# triode_control_board.net
KiCad netlist of a schematic drawn in EAGLE
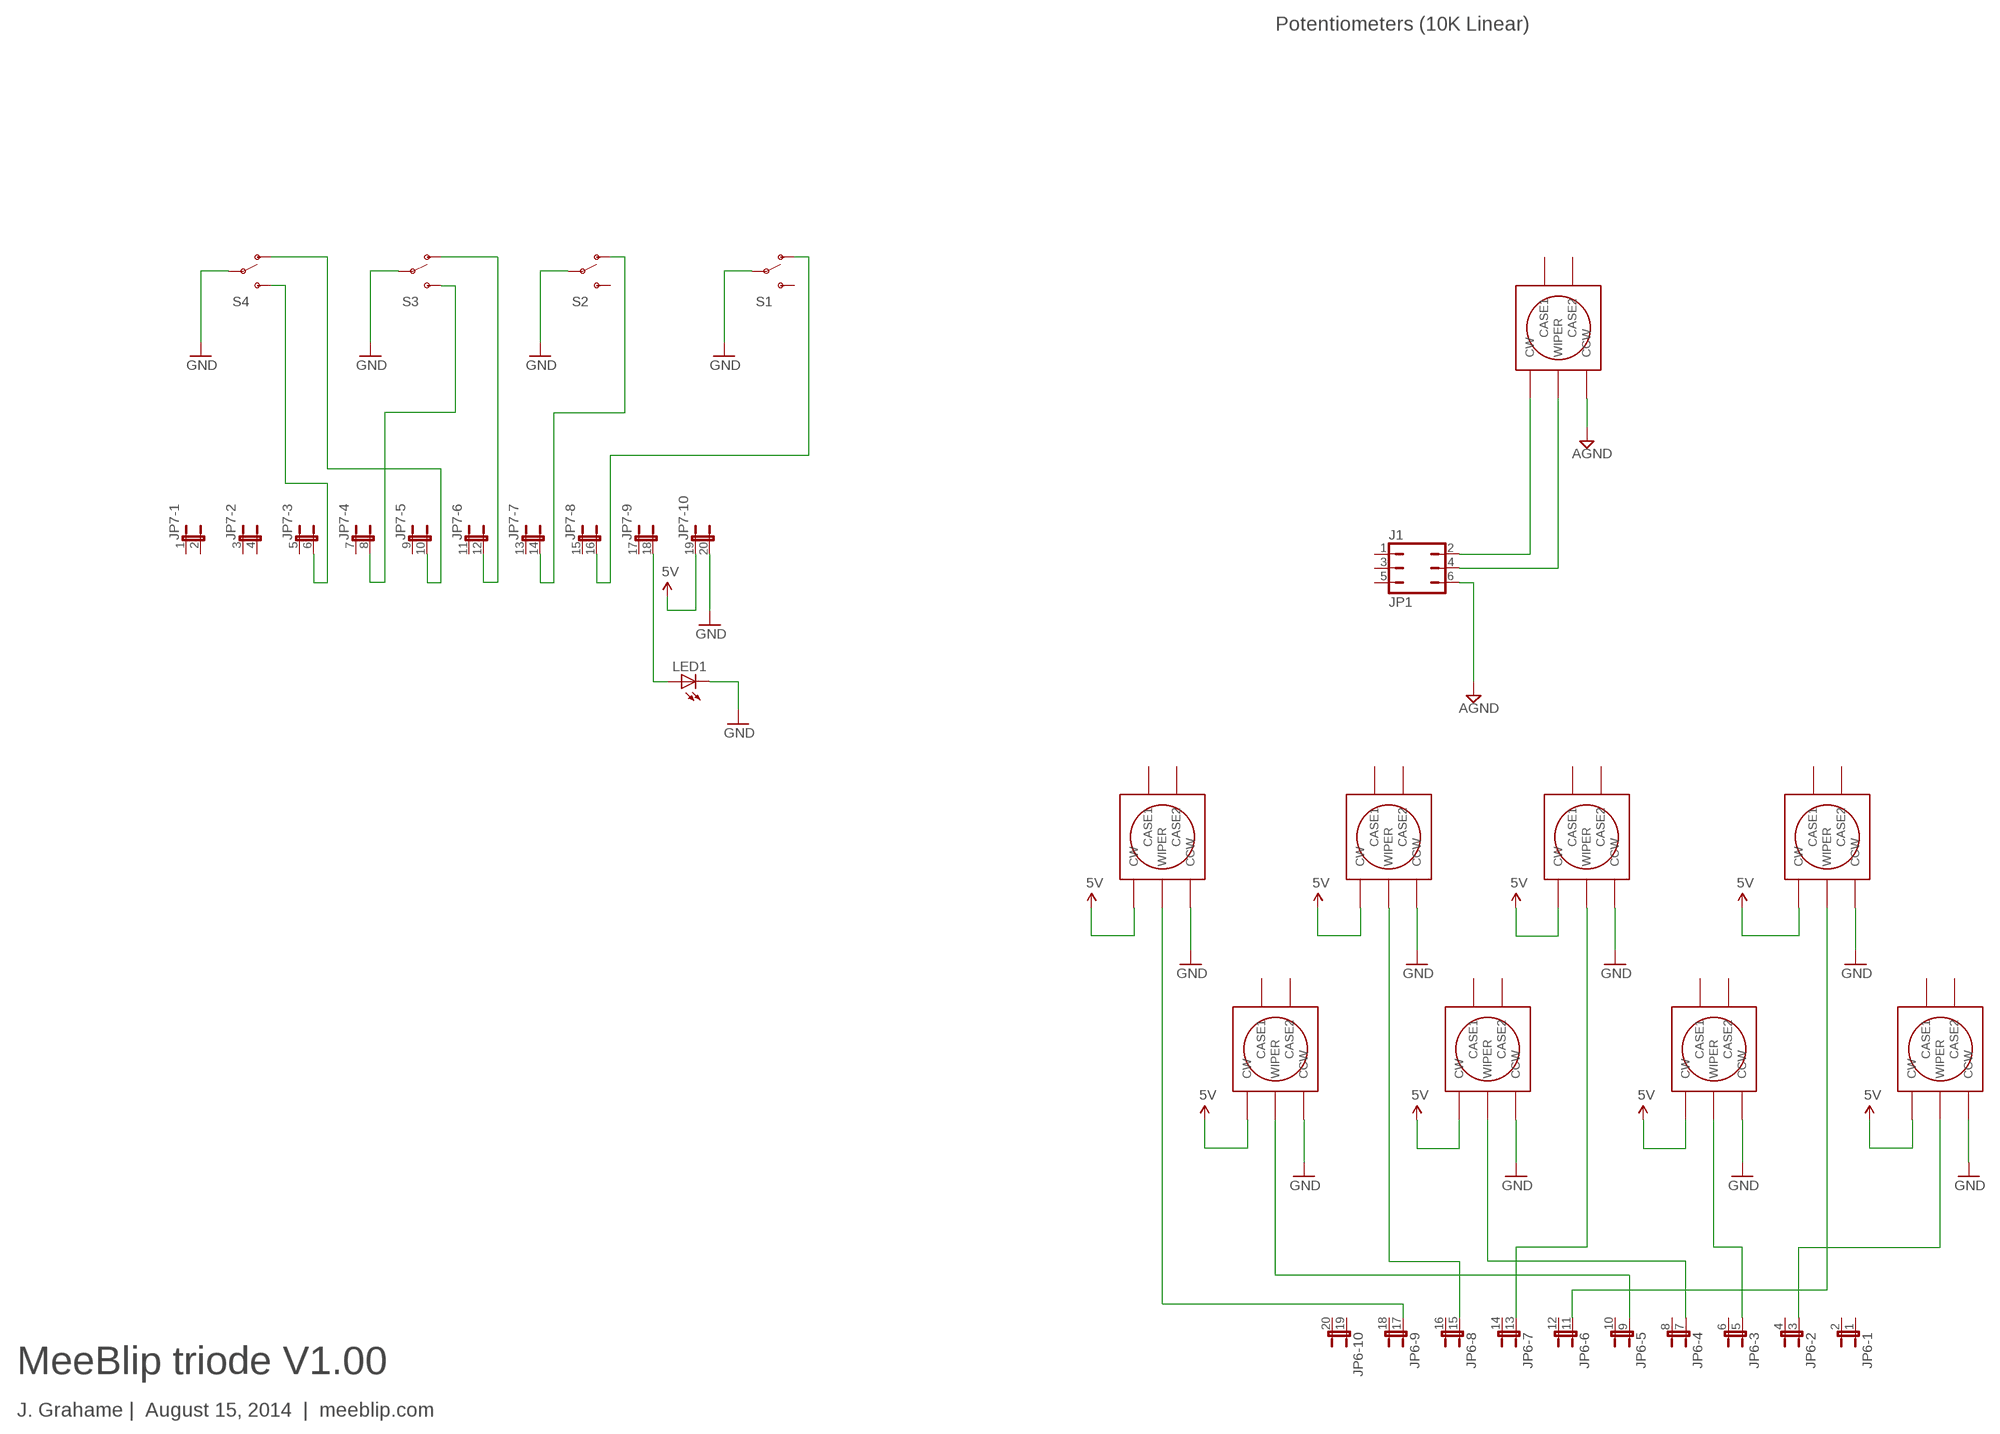
[diagram p0: schematic, sheet 1]

(export (version "E")
  (design (tool "Eeschema 10.0.6"))
  (components
    (comp (ref "J1")
      (value "JP1")
      (footprint "eagle-import:JP3Q")
      (libsource (lib "eagle-import") (part "JP3Q"))
    )
    (comp (ref "JP6")
      (value "JP10QE")
      (footprint "eagle-import:JP10Q")
      (libsource (lib "eagle-import") (part "JP10QE"))
    )
    (comp (ref "JP7")
      (value "JP10QE")
      (footprint "eagle-import:JP10Q")
      (libsource (lib "eagle-import") (part "JP10QE"))
    )
    (comp (ref "LED1")
      (value "LED3MM")
      (footprint "eagle-import:LED3MM")
      (libsource (lib "eagle-import") (part "LED3MM"))
    )
    (comp (ref "POT1")
      (value "VACOLOCO_EVUFRK09_POT")
      (footprint "eagle-import:VACOLOCO_EVUF")
      (libsource (lib "eagle-import") (part "VACOLOCO_EVUFRK09_POT"))
    )
    (comp (ref "POT2")
      (value "VACOLOCO_EVUFRK09_POT")
      (footprint "eagle-import:VACOLOCO_EVUF")
      (libsource (lib "eagle-import") (part "VACOLOCO_EVUFRK09_POT"))
    )
    (comp (ref "POT3")
      (value "VACOLOCO_EVUFRK09_POT")
      (footprint "eagle-import:VACOLOCO_EVUF")
      (libsource (lib "eagle-import") (part "VACOLOCO_EVUFRK09_POT"))
    )
    (comp (ref "POT4")
      (value "VACOLOCO_EVUFRK09_POT")
      (footprint "eagle-import:VACOLOCO_EVUF")
      (libsource (lib "eagle-import") (part "VACOLOCO_EVUFRK09_POT"))
    )
    (comp (ref "POT5")
      (value "VACOLOCO_EVUFRK09_POT")
      (footprint "eagle-import:VACOLOCO_EVUF")
      (libsource (lib "eagle-import") (part "VACOLOCO_EVUFRK09_POT"))
    )
    (comp (ref "POT6")
      (value "VACOLOCO_EVUFRK09_POT")
      (footprint "eagle-import:VACOLOCO_EVUF")
      (libsource (lib "eagle-import") (part "VACOLOCO_EVUFRK09_POT"))
    )
    (comp (ref "POT7")
      (value "VACOLOCO_EVUFRK09_POT")
      (footprint "eagle-import:VACOLOCO_EVUF")
      (libsource (lib "eagle-import") (part "VACOLOCO_EVUFRK09_POT"))
    )
    (comp (ref "POT8")
      (value "VACOLOCO_EVUFRK09_POT")
      (footprint "eagle-import:VACOLOCO_EVUF")
      (libsource (lib "eagle-import") (part "VACOLOCO_EVUFRK09_POT"))
    )
    (comp (ref "POT9")
      (value "VACOLOCO_EVUFRK09_POT")
      (footprint "eagle-import:VACOLOCO_EVUF")
      (libsource (lib "eagle-import") (part "VACOLOCO_EVUFRK09_POT"))
    )
    (comp (ref "S1")
      (value "SWITCH-SPDT")
      (footprint "eagle-import:MTS-102-A2")
      (libsource (lib "eagle-import") (part "SWITCH-SPDT"))
    )
    (comp (ref "S2")
      (value "SWITCH-SPDT")
      (footprint "eagle-import:MTS-102-A2")
      (libsource (lib "eagle-import") (part "SWITCH-SPDT"))
    )
    (comp (ref "S3")
      (value "SWITCH-SPDT")
      (footprint "eagle-import:MTS-102-A2")
      (libsource (lib "eagle-import") (part "SWITCH-SPDT"))
    )
    (comp (ref "S4")
      (value "SWITCH-SPDT")
      (footprint "eagle-import:MTS-102-A2")
      (libsource (lib "eagle-import") (part "SWITCH-SPDT"))
    )
  )
  (nets
    (net (code "1") (name "5V") (class "Default")
      (node (ref "JP7") (pin "19") (pinfunction "1_19") (pintype "passive"))
      (node (ref "POT2") (pin "CW") (pinfunction "CW_CW") (pintype "bidirectional"))
      (node (ref "POT3") (pin "CW") (pinfunction "CW_CW") (pintype "bidirectional"))
      (node (ref "POT4") (pin "CW") (pinfunction "CW_CW") (pintype "bidirectional"))
      (node (ref "POT5") (pin "CW") (pinfunction "CW_CW") (pintype "bidirectional"))
      (node (ref "POT6") (pin "CW") (pinfunction "CW_CW") (pintype "bidirectional"))
      (node (ref "POT7") (pin "CW") (pinfunction "CW_CW") (pintype "bidirectional"))
      (node (ref "POT8") (pin "CW") (pinfunction "CW_CW") (pintype "bidirectional"))
      (node (ref "POT9") (pin "CW") (pinfunction "CW_CW") (pintype "bidirectional"))
    )
    (net (code "2") (name "AGND") (class "Default")
      (node (ref "J1") (pin "6") (pinfunction "6_6") (pintype "passive"))
      (node (ref "POT1") (pin "CCW") (pinfunction "CCW_CCW") (pintype "bidirectional"))
    )
    (net (code "3") (name "GND") (class "Default")
      (node (ref "JP7") (pin "20") (pinfunction "2_20") (pintype "passive"))
      (node (ref "LED1") (pin "K") (pinfunction "C_K") (pintype "passive"))
      (node (ref "POT2") (pin "CCW") (pinfunction "CCW_CCW") (pintype "bidirectional"))
      (node (ref "POT3") (pin "CCW") (pinfunction "CCW_CCW") (pintype "bidirectional"))
      (node (ref "POT4") (pin "CCW") (pinfunction "CCW_CCW") (pintype "bidirectional"))
      (node (ref "POT5") (pin "CCW") (pinfunction "CCW_CCW") (pintype "bidirectional"))
      (node (ref "POT6") (pin "CCW") (pinfunction "CCW_CCW") (pintype "bidirectional"))
      (node (ref "POT7") (pin "CCW") (pinfunction "CCW_CCW") (pintype "bidirectional"))
      (node (ref "POT8") (pin "CCW") (pinfunction "CCW_CCW") (pintype "bidirectional"))
      (node (ref "POT9") (pin "CCW") (pinfunction "CCW_CCW") (pintype "bidirectional"))
      (node (ref "S1") (pin "2") (pinfunction "P_2") (pintype "passive"))
      (node (ref "S2") (pin "2") (pinfunction "P_2") (pintype "passive"))
      (node (ref "S3") (pin "2") (pinfunction "P_2") (pintype "passive"))
      (node (ref "S4") (pin "2") (pinfunction "P_2") (pintype "passive"))
    )
    (net (code "4") (name "Net-(J1-Pad2)") (class "Default")
      (node (ref "J1") (pin "2") (pinfunction "2_2") (pintype "passive"))
      (node (ref "POT1") (pin "CW") (pinfunction "CW_CW") (pintype "bidirectional"))
    )
    (net (code "5") (name "Net-(J1-Pad4)") (class "Default")
      (node (ref "J1") (pin "4") (pinfunction "4_4") (pintype "passive"))
      (node (ref "POT1") (pin "WIPER") (pinfunction "WIPER_WIPER") (pintype "bidirectional"))
    )
    (net (code "6") (name "Net-(JP6C-1)") (class "Default")
      (node (ref "JP6") (pin "3") (pinfunction "1_3") (pintype "passive"))
      (node (ref "POT9") (pin "WIPER") (pinfunction "WIPER_WIPER") (pintype "bidirectional"))
    )
    (net (code "7") (name "Net-(JP6D-1)") (class "Default")
      (node (ref "JP6") (pin "5") (pinfunction "1_5") (pintype "passive"))
      (node (ref "POT8") (pin "WIPER") (pinfunction "WIPER_WIPER") (pintype "bidirectional"))
    )
    (net (code "8") (name "Net-(JP6E-1)") (class "Default")
      (node (ref "JP6") (pin "7") (pinfunction "1_7") (pintype "passive"))
      (node (ref "POT7") (pin "WIPER") (pinfunction "WIPER_WIPER") (pintype "bidirectional"))
    )
    (net (code "9") (name "Net-(JP6F-1)") (class "Default")
      (node (ref "JP6") (pin "9") (pinfunction "1_9") (pintype "passive"))
      (node (ref "POT6") (pin "WIPER") (pinfunction "WIPER_WIPER") (pintype "bidirectional"))
    )
    (net (code "10") (name "Net-(JP6G-1)") (class "Default")
      (node (ref "JP6") (pin "11") (pinfunction "1_11") (pintype "passive"))
      (node (ref "POT5") (pin "WIPER") (pinfunction "WIPER_WIPER") (pintype "bidirectional"))
    )
    (net (code "11") (name "Net-(JP6H-1)") (class "Default")
      (node (ref "JP6") (pin "13") (pinfunction "1_13") (pintype "passive"))
      (node (ref "POT4") (pin "WIPER") (pinfunction "WIPER_WIPER") (pintype "bidirectional"))
    )
    (net (code "12") (name "Net-(JP6I-1)") (class "Default")
      (node (ref "JP6") (pin "15") (pinfunction "1_15") (pintype "passive"))
      (node (ref "POT3") (pin "WIPER") (pinfunction "WIPER_WIPER") (pintype "bidirectional"))
    )
    (net (code "13") (name "Net-(JP6J-1)") (class "Default")
      (node (ref "JP6") (pin "17") (pinfunction "1_17") (pintype "passive"))
      (node (ref "POT2") (pin "WIPER") (pinfunction "WIPER_WIPER") (pintype "bidirectional"))
    )
    (net (code "14") (name "Net-(JP7D-2)") (class "Default")
      (node (ref "JP7") (pin "6") (pinfunction "2_6") (pintype "passive"))
      (node (ref "S4") (pin "3") (pinfunction "S_3") (pintype "passive"))
    )
    (net (code "15") (name "Net-(JP7E-2)") (class "Default")
      (node (ref "JP7") (pin "8") (pinfunction "2_8") (pintype "passive"))
      (node (ref "S3") (pin "3") (pinfunction "S_3") (pintype "passive"))
    )
    (net (code "16") (name "Net-(JP7F-2)") (class "Default")
      (node (ref "JP7") (pin "10") (pinfunction "2_10") (pintype "passive"))
      (node (ref "S4") (pin "1") (pinfunction "O_1") (pintype "passive"))
    )
    (net (code "17") (name "Net-(JP7G-2)") (class "Default")
      (node (ref "JP7") (pin "12") (pinfunction "2_12") (pintype "passive"))
      (node (ref "S3") (pin "1") (pinfunction "O_1") (pintype "passive"))
    )
    (net (code "18") (name "Net-(JP7H-2)") (class "Default")
      (node (ref "JP7") (pin "14") (pinfunction "2_14") (pintype "passive"))
      (node (ref "S2") (pin "1") (pinfunction "O_1") (pintype "passive"))
    )
    (net (code "19") (name "Net-(JP7I-2)") (class "Default")
      (node (ref "JP7") (pin "16") (pinfunction "2_16") (pintype "passive"))
      (node (ref "S1") (pin "1") (pinfunction "O_1") (pintype "passive"))
    )
    (net (code "20") (name "Net-(JP7J-2)") (class "Default")
      (node (ref "JP7") (pin "18") (pinfunction "2_18") (pintype "passive"))
      (node (ref "LED1") (pin "A") (pinfunction "A_A") (pintype "passive"))
    )
    (net (code "21") (name "unconnected-(J1-Pad1)") (class "Default")
      (node (ref "J1") (pin "1") (pinfunction "1_1") (pintype "passive"))
    )
    (net (code "22") (name "unconnected-(J1-Pad3)") (class "Default")
      (node (ref "J1") (pin "3") (pinfunction "3_3") (pintype "passive"))
    )
    (net (code "23") (name "unconnected-(J1-Pad5)") (class "Default")
      (node (ref "J1") (pin "5") (pinfunction "5_5") (pintype "passive"))
    )
    (net (code "24") (name "unconnected-(JP6-Pad1)") (class "Default")
      (node (ref "JP6") (pin "1") (pinfunction "1_1") (pintype "passive"))
    )
    (net (code "25") (name "unconnected-(JP6-Pad2)") (class "Default")
      (node (ref "JP6") (pin "2") (pinfunction "2_2") (pintype "passive"))
    )
    (net (code "26") (name "unconnected-(JP6B-1-Pad19)") (class "Default")
      (node (ref "JP6") (pin "19") (pinfunction "1_19") (pintype "passive"))
    )
    (net (code "27") (name "unconnected-(JP6B-2-Pad20)") (class "Default")
      (node (ref "JP6") (pin "20") (pinfunction "2_20") (pintype "passive"))
    )
    (net (code "28") (name "unconnected-(JP6C-2-Pad4)") (class "Default")
      (node (ref "JP6") (pin "4") (pinfunction "2_4") (pintype "passive"))
    )
    (net (code "29") (name "unconnected-(JP6D-2-Pad6)") (class "Default")
      (node (ref "JP6") (pin "6") (pinfunction "2_6") (pintype "passive"))
    )
    (net (code "30") (name "unconnected-(JP6E-2-Pad8)") (class "Default")
      (node (ref "JP6") (pin "8") (pinfunction "2_8") (pintype "passive"))
    )
    (net (code "31") (name "unconnected-(JP6F-2-Pad10)") (class "Default")
      (node (ref "JP6") (pin "10") (pinfunction "2_10") (pintype "passive"))
    )
    (net (code "32") (name "unconnected-(JP6G-2-Pad12)") (class "Default")
      (node (ref "JP6") (pin "12") (pinfunction "2_12") (pintype "passive"))
    )
    (net (code "33") (name "unconnected-(JP6H-2-Pad14)") (class "Default")
      (node (ref "JP6") (pin "14") (pinfunction "2_14") (pintype "passive"))
    )
    (net (code "34") (name "unconnected-(JP6I-2-Pad16)") (class "Default")
      (node (ref "JP6") (pin "16") (pinfunction "2_16") (pintype "passive"))
    )
    (net (code "35") (name "unconnected-(JP6J-2-Pad18)") (class "Default")
      (node (ref "JP6") (pin "18") (pinfunction "2_18") (pintype "passive"))
    )
    (net (code "36") (name "unconnected-(JP7-Pad1)") (class "Default")
      (node (ref "JP7") (pin "1") (pinfunction "1_1") (pintype "passive"))
    )
    (net (code "37") (name "unconnected-(JP7-Pad2)") (class "Default")
      (node (ref "JP7") (pin "2") (pinfunction "2_2") (pintype "passive"))
    )
    (net (code "38") (name "unconnected-(JP7C-1-Pad3)") (class "Default")
      (node (ref "JP7") (pin "3") (pinfunction "1_3") (pintype "passive"))
    )
    (net (code "39") (name "unconnected-(JP7C-2-Pad4)") (class "Default")
      (node (ref "JP7") (pin "4") (pinfunction "2_4") (pintype "passive"))
    )
    (net (code "40") (name "unconnected-(JP7D-1-Pad5)") (class "Default")
      (node (ref "JP7") (pin "5") (pinfunction "1_5") (pintype "passive"))
    )
    (net (code "41") (name "unconnected-(JP7E-1-Pad7)") (class "Default")
      (node (ref "JP7") (pin "7") (pinfunction "1_7") (pintype "passive"))
    )
    (net (code "42") (name "unconnected-(JP7F-1-Pad9)") (class "Default")
      (node (ref "JP7") (pin "9") (pinfunction "1_9") (pintype "passive"))
    )
    (net (code "43") (name "unconnected-(JP7G-1-Pad11)") (class "Default")
      (node (ref "JP7") (pin "11") (pinfunction "1_11") (pintype "passive"))
    )
    (net (code "44") (name "unconnected-(JP7H-1-Pad13)") (class "Default")
      (node (ref "JP7") (pin "13") (pinfunction "1_13") (pintype "passive"))
    )
    (net (code "45") (name "unconnected-(JP7I-1-Pad15)") (class "Default")
      (node (ref "JP7") (pin "15") (pinfunction "1_15") (pintype "passive"))
    )
    (net (code "46") (name "unconnected-(JP7J-1-Pad17)") (class "Default")
      (node (ref "JP7") (pin "17") (pinfunction "1_17") (pintype "passive"))
    )
    (net (code "47") (name "unconnected-(POT1-PadCASE1)") (class "Default")
      (node (ref "POT1") (pin "CASE1") (pinfunction "CASE1_CASE1") (pintype "bidirectional"))
    )
    (net (code "48") (name "unconnected-(POT1-PadCASE2)") (class "Default")
      (node (ref "POT1") (pin "CASE2") (pinfunction "CASE2_CASE2") (pintype "bidirectional"))
    )
    (net (code "49") (name "unconnected-(POT2-PadCASE1)") (class "Default")
      (node (ref "POT2") (pin "CASE1") (pinfunction "CASE1_CASE1") (pintype "bidirectional"))
    )
    (net (code "50") (name "unconnected-(POT2-PadCASE2)") (class "Default")
      (node (ref "POT2") (pin "CASE2") (pinfunction "CASE2_CASE2") (pintype "bidirectional"))
    )
    (net (code "51") (name "unconnected-(POT3-PadCASE1)") (class "Default")
      (node (ref "POT3") (pin "CASE1") (pinfunction "CASE1_CASE1") (pintype "bidirectional"))
    )
    (net (code "52") (name "unconnected-(POT3-PadCASE2)") (class "Default")
      (node (ref "POT3") (pin "CASE2") (pinfunction "CASE2_CASE2") (pintype "bidirectional"))
    )
    (net (code "53") (name "unconnected-(POT4-PadCASE1)") (class "Default")
      (node (ref "POT4") (pin "CASE1") (pinfunction "CASE1_CASE1") (pintype "bidirectional"))
    )
    (net (code "54") (name "unconnected-(POT4-PadCASE2)") (class "Default")
      (node (ref "POT4") (pin "CASE2") (pinfunction "CASE2_CASE2") (pintype "bidirectional"))
    )
    (net (code "55") (name "unconnected-(POT5-PadCASE1)") (class "Default")
      (node (ref "POT5") (pin "CASE1") (pinfunction "CASE1_CASE1") (pintype "bidirectional"))
    )
    (net (code "56") (name "unconnected-(POT5-PadCASE2)") (class "Default")
      (node (ref "POT5") (pin "CASE2") (pinfunction "CASE2_CASE2") (pintype "bidirectional"))
    )
    (net (code "57") (name "unconnected-(POT6-PadCASE1)") (class "Default")
      (node (ref "POT6") (pin "CASE1") (pinfunction "CASE1_CASE1") (pintype "bidirectional"))
    )
    (net (code "58") (name "unconnected-(POT6-PadCASE2)") (class "Default")
      (node (ref "POT6") (pin "CASE2") (pinfunction "CASE2_CASE2") (pintype "bidirectional"))
    )
    (net (code "59") (name "unconnected-(POT7-PadCASE1)") (class "Default")
      (node (ref "POT7") (pin "CASE1") (pinfunction "CASE1_CASE1") (pintype "bidirectional"))
    )
    (net (code "60") (name "unconnected-(POT7-PadCASE2)") (class "Default")
      (node (ref "POT7") (pin "CASE2") (pinfunction "CASE2_CASE2") (pintype "bidirectional"))
    )
    (net (code "61") (name "unconnected-(POT8-PadCASE1)") (class "Default")
      (node (ref "POT8") (pin "CASE1") (pinfunction "CASE1_CASE1") (pintype "bidirectional"))
    )
    (net (code "62") (name "unconnected-(POT8-PadCASE2)") (class "Default")
      (node (ref "POT8") (pin "CASE2") (pinfunction "CASE2_CASE2") (pintype "bidirectional"))
    )
    (net (code "63") (name "unconnected-(POT9-PadCASE1)") (class "Default")
      (node (ref "POT9") (pin "CASE1") (pinfunction "CASE1_CASE1") (pintype "bidirectional"))
    )
    (net (code "64") (name "unconnected-(POT9-PadCASE2)") (class "Default")
      (node (ref "POT9") (pin "CASE2") (pinfunction "CASE2_CASE2") (pintype "bidirectional"))
    )
    (net (code "65") (name "unconnected-(S1-S-Pad3)") (class "Default")
      (node (ref "S1") (pin "3") (pinfunction "S_3") (pintype "passive"))
    )
    (net (code "66") (name "unconnected-(S2-S-Pad3)") (class "Default")
      (node (ref "S2") (pin "3") (pinfunction "S_3") (pintype "passive"))
    )
  )
)
